# MainBoard.net
KiCad netlist of a schematic drawn in EAGLE
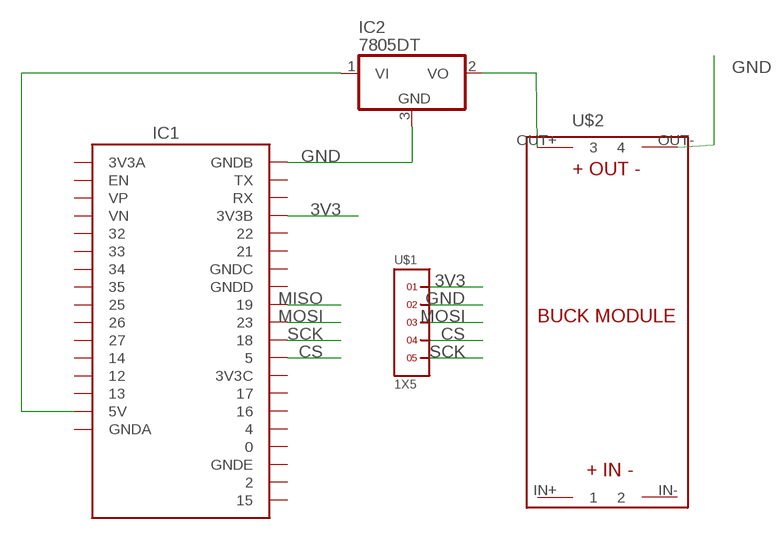
[diagram p0: schematic, sheet 1]

(export (version "E")
  (design (tool "Eeschema 10.0.6"))
  (components
    (comp (ref "IC1")
      (value "SSFD_LOLIN32_WEMOS_CHINA_W_BATT")
      (footprint "eagle-import:SSFD_LOLIN32_WEMOS_CHINA_W_BATT")
      (libsource (lib "eagle-import") (part "SSFD_LOLIN32_WEMOS_CHINA_W_BATT"))
    )
    (comp (ref "IC2")
      (value "7805DT")
      (footprint "eagle-import:TO252")
      (libsource (lib "eagle-import") (part "78DT05"))
    )
    (comp (ref "U$1")
      (value "1X5")
      (footprint "eagle-import:1X5")
      (libsource (lib "eagle-import") (part "1X5"))
    )
    (comp (ref "U$2")
      (value "BUCK_MODULE")
      (footprint "eagle-import:BUCK_MODULE_SMALL")
      (libsource (lib "eagle-import") (part "BUCK_MODULE"))
    )
  )
  (nets
    (net (code "1") (name "/3V3") (class "Default")
      (node (ref "IC1") (pin "3V3B") (pinfunction "3V3B_3V3B") (pintype "bidirectional"))
      (node (ref "U$1") (pin "1") (pinfunction "1_1") (pintype "bidirectional"))
    )
    (net (code "2") (name "/CS") (class "Default")
      (node (ref "IC1") (pin "5") (pinfunction "5_5") (pintype "bidirectional"))
      (node (ref "U$1") (pin "4") (pinfunction "4_4") (pintype "bidirectional"))
    )
    (net (code "3") (name "/GND") (class "Default")
      (node (ref "IC1") (pin "GNDB") (pinfunction "GNDB_GNDB") (pintype "bidirectional"))
      (node (ref "IC2") (pin "3") (pinfunction "GND_3") (pintype "passive"))
      (node (ref "U$1") (pin "2") (pinfunction "2_2") (pintype "bidirectional"))
      (node (ref "U$2") (pin "OUT-") (pinfunction "4_OUT-") (pintype "bidirectional"))
    )
    (net (code "4") (name "/MISO") (class "Default")
      (node (ref "IC1") (pin "19") (pinfunction "19_19") (pintype "bidirectional"))
    )
    (net (code "5") (name "/MOSI") (class "Default")
      (node (ref "IC1") (pin "23") (pinfunction "23_23") (pintype "bidirectional"))
      (node (ref "U$1") (pin "3") (pinfunction "3_3") (pintype "bidirectional"))
    )
    (net (code "6") (name "/SCK") (class "Default")
      (node (ref "IC1") (pin "18") (pinfunction "18_18") (pintype "bidirectional"))
      (node (ref "U$1") (pin "5") (pinfunction "5_5") (pintype "bidirectional"))
    )
    (net (code "7") (name "Net-(IC2-VI)") (class "Default")
      (node (ref "IC1") (pin "5V") (pinfunction "5V_5V") (pintype "bidirectional"))
      (node (ref "IC2") (pin "1") (pinfunction "VI_1") (pintype "input"))
    )
    (net (code "8") (name "Net-(IC2-VO)") (class "Default")
      (node (ref "IC2") (pin "2") (pinfunction "VO_2") (pintype "passive"))
      (node (ref "U$2") (pin "OUT+") (pinfunction "3_OUT+") (pintype "bidirectional"))
    )
    (net (code "9") (name "unconnected-(IC1-Pad0)") (class "Default")
      (node (ref "IC1") (pin "0") (pinfunction "0_0") (pintype "bidirectional"))
    )
    (net (code "10") (name "unconnected-(IC1-Pad2)") (class "Default")
      (node (ref "IC1") (pin "2") (pinfunction "2_2") (pintype "bidirectional"))
    )
    (net (code "11") (name "unconnected-(IC1-Pad3V3A)") (class "Default")
      (node (ref "IC1") (pin "3V3A") (pinfunction "3V3A_3V3A") (pintype "bidirectional"))
    )
    (net (code "12") (name "unconnected-(IC1-Pad3V3C)") (class "Default")
      (node (ref "IC1") (pin "3V3C") (pinfunction "3V3C_3V3C") (pintype "bidirectional"))
    )
    (net (code "13") (name "unconnected-(IC1-Pad4)") (class "Default")
      (node (ref "IC1") (pin "4") (pinfunction "4_4") (pintype "bidirectional"))
    )
    (net (code "14") (name "unconnected-(IC1-Pad12)") (class "Default")
      (node (ref "IC1") (pin "12") (pinfunction "12_12") (pintype "bidirectional"))
    )
    (net (code "15") (name "unconnected-(IC1-Pad13)") (class "Default")
      (node (ref "IC1") (pin "13") (pinfunction "13_13") (pintype "bidirectional"))
    )
    (net (code "16") (name "unconnected-(IC1-Pad14)") (class "Default")
      (node (ref "IC1") (pin "14") (pinfunction "14_14") (pintype "bidirectional"))
    )
    (net (code "17") (name "unconnected-(IC1-Pad15)") (class "Default")
      (node (ref "IC1") (pin "15") (pinfunction "15_15") (pintype "bidirectional"))
    )
    (net (code "18") (name "unconnected-(IC1-Pad16)") (class "Default")
      (node (ref "IC1") (pin "16") (pinfunction "16_16") (pintype "bidirectional"))
    )
    (net (code "19") (name "unconnected-(IC1-Pad17)") (class "Default")
      (node (ref "IC1") (pin "17") (pinfunction "17_17") (pintype "bidirectional"))
    )
    (net (code "20") (name "unconnected-(IC1-Pad21)") (class "Default")
      (node (ref "IC1") (pin "21") (pinfunction "21_21") (pintype "bidirectional"))
    )
    (net (code "21") (name "unconnected-(IC1-Pad22)") (class "Default")
      (node (ref "IC1") (pin "22") (pinfunction "22_22") (pintype "bidirectional"))
    )
    (net (code "22") (name "unconnected-(IC1-Pad25)") (class "Default")
      (node (ref "IC1") (pin "25") (pinfunction "25_25") (pintype "bidirectional"))
    )
    (net (code "23") (name "unconnected-(IC1-Pad26)") (class "Default")
      (node (ref "IC1") (pin "26") (pinfunction "26_26") (pintype "bidirectional"))
    )
    (net (code "24") (name "unconnected-(IC1-Pad27)") (class "Default")
      (node (ref "IC1") (pin "27") (pinfunction "27_27") (pintype "bidirectional"))
    )
    (net (code "25") (name "unconnected-(IC1-Pad32)") (class "Default")
      (node (ref "IC1") (pin "32") (pinfunction "32_32") (pintype "bidirectional"))
    )
    (net (code "26") (name "unconnected-(IC1-Pad33)") (class "Default")
      (node (ref "IC1") (pin "33") (pinfunction "33_33") (pintype "bidirectional"))
    )
    (net (code "27") (name "unconnected-(IC1-Pad34)") (class "Default")
      (node (ref "IC1") (pin "34") (pinfunction "34_34") (pintype "bidirectional"))
    )
    (net (code "28") (name "unconnected-(IC1-Pad35)") (class "Default")
      (node (ref "IC1") (pin "35") (pinfunction "35_35") (pintype "bidirectional"))
    )
    (net (code "29") (name "unconnected-(IC1-PadEN)") (class "Default")
      (node (ref "IC1") (pin "EN") (pinfunction "EN_EN") (pintype "bidirectional"))
    )
    (net (code "30") (name "unconnected-(IC1-PadGNDA)") (class "Default")
      (node (ref "IC1") (pin "GNDA") (pinfunction "GNDA_GNDA") (pintype "bidirectional"))
    )
    (net (code "31") (name "unconnected-(IC1-PadGNDC)") (class "Default")
      (node (ref "IC1") (pin "GNDC") (pinfunction "GNDC_GNDC") (pintype "bidirectional"))
    )
    (net (code "32") (name "unconnected-(IC1-PadGNDD)") (class "Default")
      (node (ref "IC1") (pin "GNDD") (pinfunction "GNDD_GNDD") (pintype "bidirectional"))
    )
    (net (code "33") (name "unconnected-(IC1-PadGNDE)") (class "Default")
      (node (ref "IC1") (pin "GNDE") (pinfunction "GNDE_GNDE") (pintype "bidirectional"))
    )
    (net (code "34") (name "unconnected-(IC1-PadRX)") (class "Default")
      (node (ref "IC1") (pin "RX") (pinfunction "RX_RX") (pintype "bidirectional"))
    )
    (net (code "35") (name "unconnected-(IC1-PadTX)") (class "Default")
      (node (ref "IC1") (pin "TX") (pinfunction "TX_TX") (pintype "bidirectional"))
    )
    (net (code "36") (name "unconnected-(IC1-PadVN)") (class "Default")
      (node (ref "IC1") (pin "VN") (pinfunction "VN_VN") (pintype "bidirectional"))
    )
    (net (code "37") (name "unconnected-(IC1-PadVP)") (class "Default")
      (node (ref "IC1") (pin "VP") (pinfunction "VP_VP") (pintype "bidirectional"))
    )
    (net (code "38") (name "unconnected-(U$2-1-PadIN+)") (class "Default")
      (node (ref "U$2") (pin "IN+") (pinfunction "1_IN+") (pintype "bidirectional"))
    )
    (net (code "39") (name "unconnected-(U$2-2-PadIN-)") (class "Default")
      (node (ref "U$2") (pin "IN-") (pinfunction "2_IN-") (pintype "bidirectional"))
    )
  )
)
